# CCM_0024.net
KiCad netlist of a schematic drawn in EAGLE
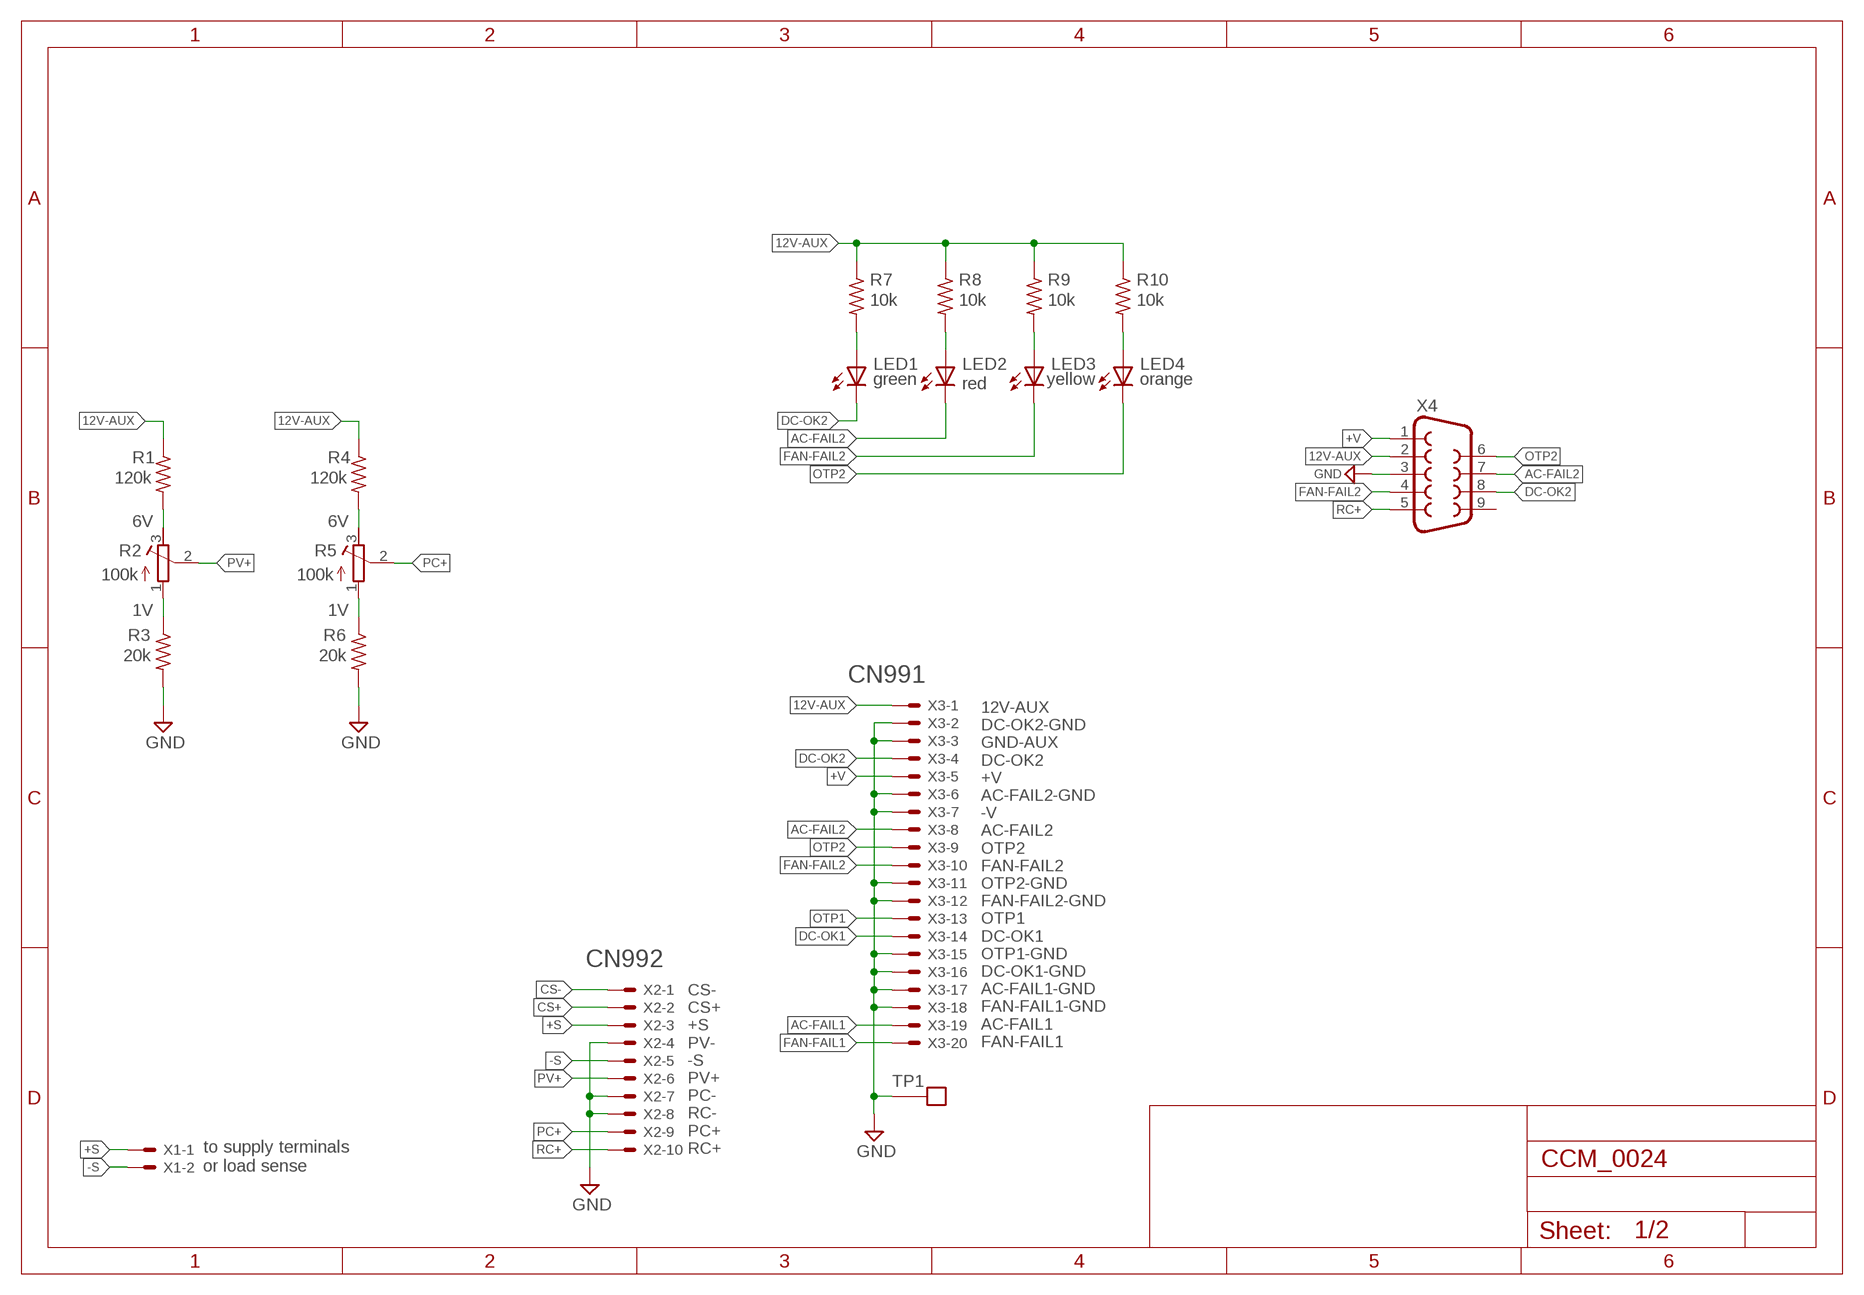
[diagram p0: schematic, sheet 1]
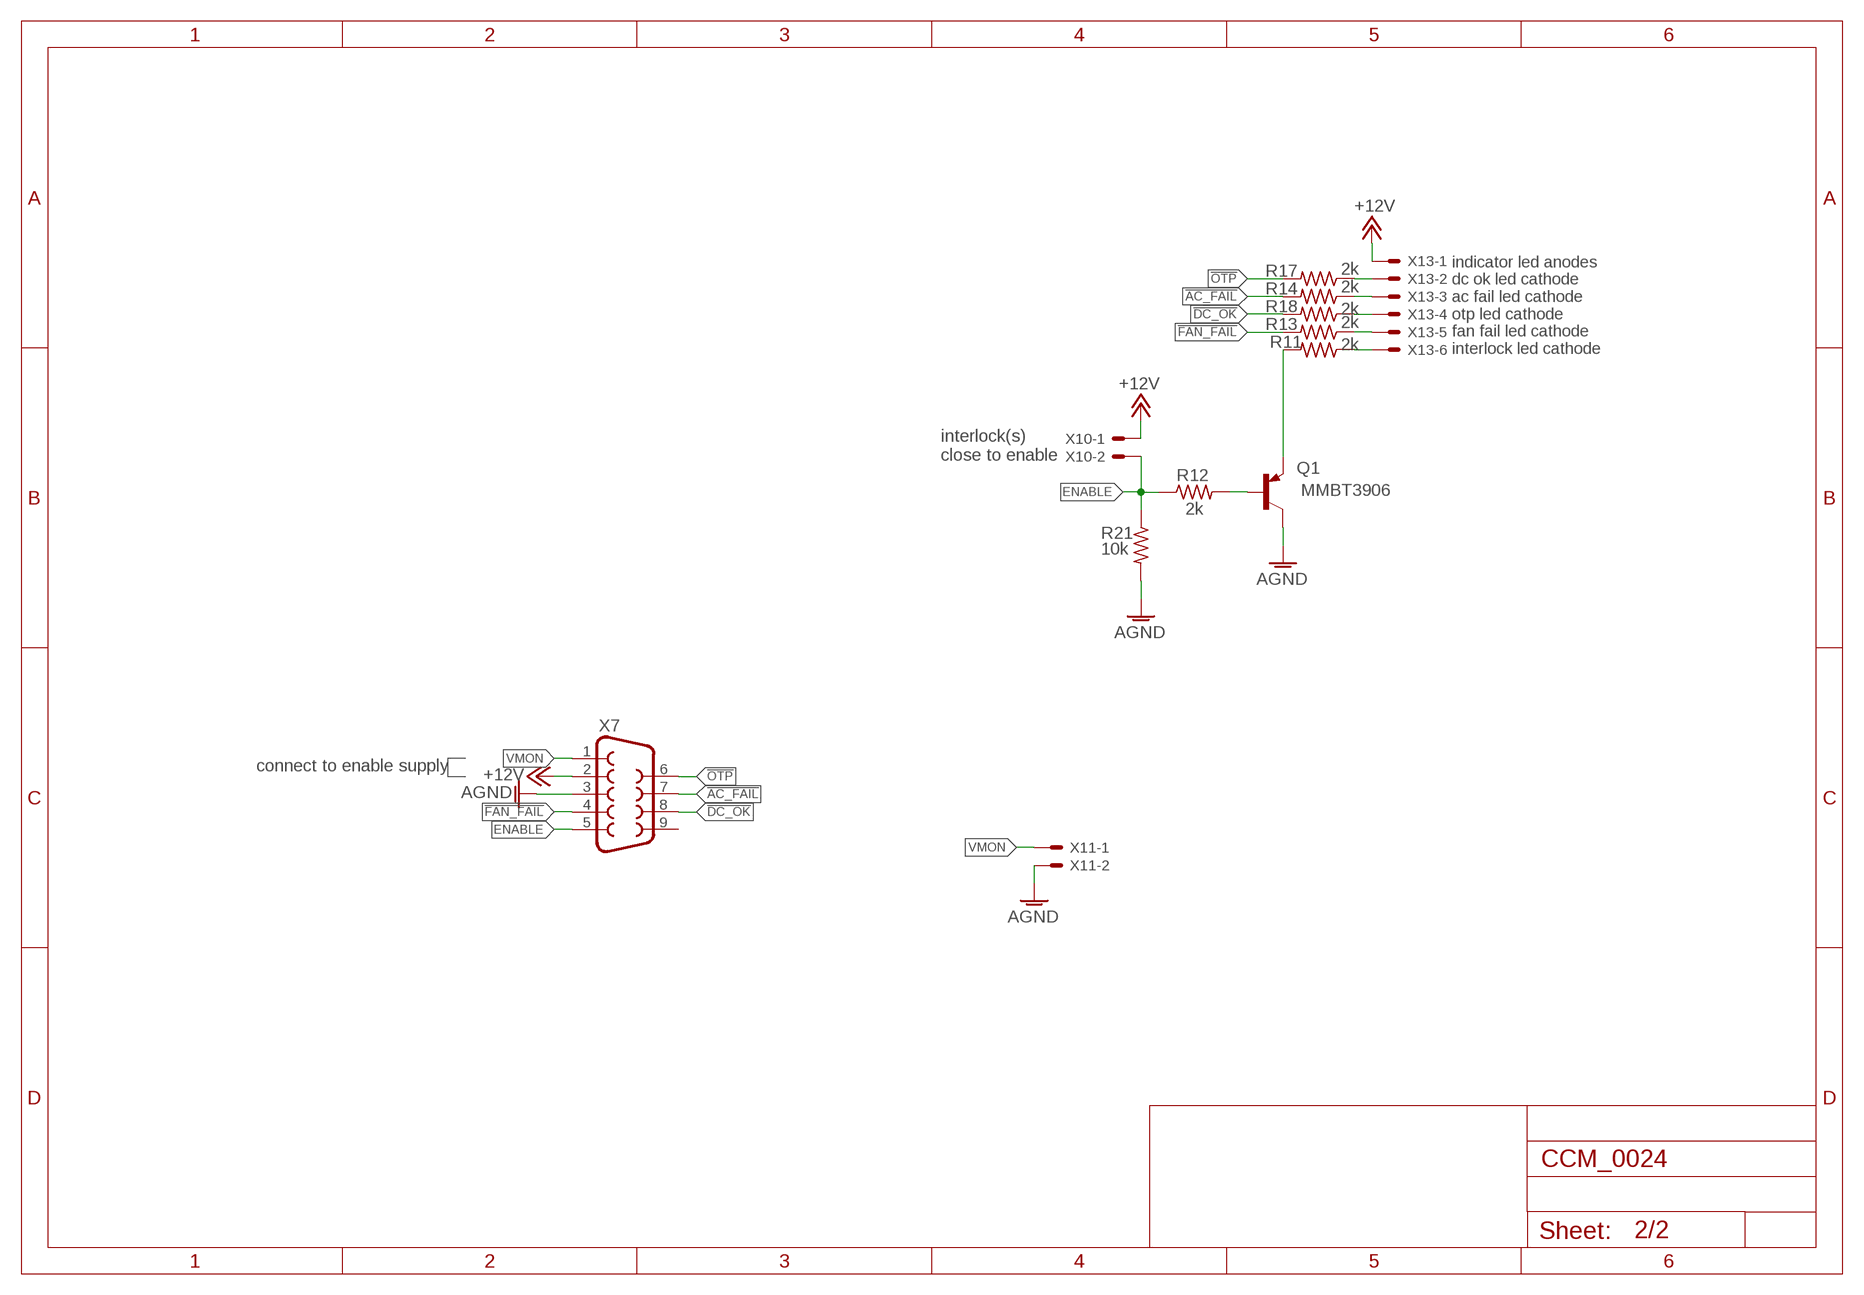
[diagram p1: schematic, sheet 2]

(export (version "E")
  (design (tool "Eeschema 10.0.6"))
  (components
    (comp (ref "Q1")
      (value "MMBT3906")
      (footprint "eagle-import:SOT23-BEC")
      (libsource (lib "eagle-import") (part "MMBT3906SMDLT1"))
    )
    (comp (ref "R11")
      (value "2k")
      (footprint "eagle-import:0603")
      (libsource (lib "eagle-import") (part "R0603"))
    )
    (comp (ref "R12")
      (value "2k")
      (footprint "eagle-import:0603")
      (libsource (lib "eagle-import") (part "R0603"))
    )
    (comp (ref "R13")
      (value "2k")
      (footprint "eagle-import:0603")
      (libsource (lib "eagle-import") (part "R0603"))
    )
    (comp (ref "R14")
      (value "2k")
      (footprint "eagle-import:0603")
      (libsource (lib "eagle-import") (part "R0603"))
    )
    (comp (ref "R17")
      (value "2k")
      (footprint "eagle-import:0603")
      (libsource (lib "eagle-import") (part "R0603"))
    )
    (comp (ref "R18")
      (value "2k")
      (footprint "eagle-import:0603")
      (libsource (lib "eagle-import") (part "R0603"))
    )
    (comp (ref "R21")
      (value "10k")
      (footprint "eagle-import:0603")
      (libsource (lib "eagle-import") (part "R0603"))
    )
    (comp (ref "X7")
      (value "F09H")
      (footprint "eagle-import:F09H")
      (libsource (lib "eagle-import") (part "F09H"))
    )
    (comp (ref "X10")
      (value "22-23-2021")
      (footprint "eagle-import:22-23-2021")
      (fields (field (name "MF") "MOLEX"))
      (libsource (lib "eagle-import") (part "22-23-2021"))
    )
    (comp (ref "X11")
      (value "22-23-2021")
      (footprint "eagle-import:22-23-2021")
      (fields (field (name "MF") "MOLEX"))
      (libsource (lib "eagle-import") (part "22-23-2021"))
    )
    (comp (ref "X13")
      (value "22-23-2061")
      (footprint "eagle-import:22-23-2061")
      (fields (field (name "MF") "MOLEX"))
      (libsource (lib "eagle-import") (part "22-23-2061"))
    )
    (comp (ref "LED1")
      (value "green")
      (footprint "eagle-import:LED_SML0603")
      (libsource (lib "eagle-import") (part "LED_ESML0603"))
    )
    (comp (ref "LED2")
      (value "red")
      (footprint "eagle-import:LED_SML0603")
      (libsource (lib "eagle-import") (part "LED_ESML0603"))
    )
    (comp (ref "LED3")
      (value "yellow")
      (footprint "eagle-import:LED_SML0603")
      (libsource (lib "eagle-import") (part "LED_ESML0603"))
    )
    (comp (ref "LED4")
      (value "orange")
      (footprint "eagle-import:LED_SML0603")
      (libsource (lib "eagle-import") (part "LED_ESML0603"))
    )
    (comp (ref "R1")
      (value "120k")
      (footprint "eagle-import:0603")
      (libsource (lib "eagle-import") (part "R0603"))
    )
    (comp (ref "R2")
      (value "100k")
      (footprint "eagle-import:RTRIM3296Y")
      (libsource (lib "eagle-import") (part "R-TRIMM3296Y"))
    )
    (comp (ref "R3")
      (value "20k")
      (footprint "eagle-import:0603")
      (libsource (lib "eagle-import") (part "R0603"))
    )
    (comp (ref "R4")
      (value "120k")
      (footprint "eagle-import:0603")
      (libsource (lib "eagle-import") (part "R0603"))
    )
    (comp (ref "R5")
      (value "100k")
      (footprint "eagle-import:RTRIM3296Y")
      (libsource (lib "eagle-import") (part "R-TRIMM3296Y"))
    )
    (comp (ref "R6")
      (value "20k")
      (footprint "eagle-import:0603")
      (libsource (lib "eagle-import") (part "R0603"))
    )
    (comp (ref "R7")
      (value "10k")
      (footprint "eagle-import:0603")
      (libsource (lib "eagle-import") (part "R0603"))
    )
    (comp (ref "R8")
      (value "10k")
      (footprint "eagle-import:0603")
      (libsource (lib "eagle-import") (part "R0603"))
    )
    (comp (ref "R9")
      (value "10k")
      (footprint "eagle-import:0603")
      (libsource (lib "eagle-import") (part "R0603"))
    )
    (comp (ref "R10")
      (value "10k")
      (footprint "eagle-import:0603")
      (libsource (lib "eagle-import") (part "R0603"))
    )
    (comp (ref "TP1")
      (value "TESTPOINT")
      (footprint "eagle-import:TESTPOINT")
      (libsource (lib "eagle-import") (part "TESTPOINT"))
    )
    (comp (ref "X1")
      (value "22-23-2021")
      (footprint "eagle-import:22-23-2021")
      (fields (field (name "MF") "MOLEX"))
      (libsource (lib "eagle-import") (part "22-23-2021"))
    )
    (comp (ref "X2")
      (value "87758-1016")
      (footprint "eagle-import:87758-1016")
      (fields (field (name "MF") "MOLEX"))
      (libsource (lib "eagle-import") (part "87758-1016"))
    )
    (comp (ref "X3")
      (value "87758-2016")
      (footprint "eagle-import:87758-2016")
      (fields (field (name "MF") "MOLEX"))
      (libsource (lib "eagle-import") (part "87758-2016"))
    )
    (comp (ref "X4")
      (value "F09V")
      (footprint "eagle-import:F09V")
      (libsource (lib "eagle-import") (part "F09V"))
    )
  )
  (nets
    (net (code "1") (name "+12V") (class "Default")
      (node (ref "X10") (pin "1") (pinfunction "S_1") (pintype "passive"))
      (node (ref "X13") (pin "1") (pinfunction "S_1") (pintype "passive"))
      (node (ref "X7") (pin "2") (pinfunction "2_2") (pintype "passive"))
    )
    (net (code "2") (name "+S") (class "Default")
      (node (ref "X1") (pin "1") (pinfunction "S_1") (pintype "passive"))
      (node (ref "X2") (pin "3") (pinfunction "S_3") (pintype "passive"))
    )
    (net (code "3") (name "+V") (class "Default")
      (node (ref "X3") (pin "5") (pinfunction "S_5") (pintype "passive"))
      (node (ref "X4") (pin "1") (pinfunction "1_1") (pintype "passive"))
    )
    (net (code "4") (name "-S") (class "Default")
      (node (ref "X1") (pin "2") (pinfunction "S_2") (pintype "passive"))
      (node (ref "X2") (pin "5") (pinfunction "S_5") (pintype "passive"))
    )
    (net (code "5") (name "12V-AUX") (class "Default")
      (node (ref "R1") (pin "1") (pinfunction "1_1") (pintype "passive"))
      (node (ref "R10") (pin "1") (pinfunction "1_1") (pintype "passive"))
      (node (ref "R4") (pin "1") (pinfunction "1_1") (pintype "passive"))
      (node (ref "R7") (pin "1") (pinfunction "1_1") (pintype "passive"))
      (node (ref "R8") (pin "1") (pinfunction "1_1") (pintype "passive"))
      (node (ref "R9") (pin "1") (pinfunction "1_1") (pintype "passive"))
      (node (ref "X3") (pin "1") (pinfunction "S_1") (pintype "passive"))
      (node (ref "X4") (pin "2") (pinfunction "2_2") (pintype "passive"))
    )
    (net (code "6") (name "AC-FAIL1") (class "Default")
      (node (ref "X3") (pin "19") (pinfunction "S_19") (pintype "passive"))
    )
    (net (code "7") (name "AC-FAIL2") (class "Default")
      (node (ref "LED2") (pin "C") (pinfunction "C_C") (pintype "passive"))
      (node (ref "X3") (pin "8") (pinfunction "S_8") (pintype "passive"))
      (node (ref "X4") (pin "7") (pinfunction "7_7") (pintype "passive"))
    )
    (net (code "8") (name "AGND") (class "Default")
      (node (ref "Q1") (pin "C") (pinfunction "C_C") (pintype "passive"))
      (node (ref "R21") (pin "2") (pinfunction "2_2") (pintype "passive"))
      (node (ref "X11") (pin "2") (pinfunction "S_2") (pintype "passive"))
      (node (ref "X7") (pin "3") (pinfunction "3_3") (pintype "passive"))
    )
    (net (code "9") (name "CS+") (class "Default")
      (node (ref "X2") (pin "2") (pinfunction "S_2") (pintype "passive"))
    )
    (net (code "10") (name "CS-") (class "Default")
      (node (ref "X2") (pin "1") (pinfunction "S_1") (pintype "passive"))
    )
    (net (code "11") (name "DC-OK1") (class "Default")
      (node (ref "X3") (pin "14") (pinfunction "S_14") (pintype "passive"))
    )
    (net (code "12") (name "DC-OK2") (class "Default")
      (node (ref "LED1") (pin "C") (pinfunction "C_C") (pintype "passive"))
      (node (ref "X3") (pin "4") (pinfunction "S_4") (pintype "passive"))
      (node (ref "X4") (pin "8") (pinfunction "8_8") (pintype "passive"))
    )
    (net (code "13") (name "ENABLE") (class "Default")
      (node (ref "R12") (pin "1") (pinfunction "1_1") (pintype "passive"))
      (node (ref "R21") (pin "1") (pinfunction "1_1") (pintype "passive"))
      (node (ref "X10") (pin "2") (pinfunction "S_2") (pintype "passive"))
      (node (ref "X7") (pin "5") (pinfunction "5_5") (pintype "passive"))
    )
    (net (code "14") (name "FAN-FAIL1") (class "Default")
      (node (ref "X3") (pin "20") (pinfunction "S_20") (pintype "passive"))
    )
    (net (code "15") (name "FAN-FAIL2") (class "Default")
      (node (ref "LED3") (pin "C") (pinfunction "C_C") (pintype "passive"))
      (node (ref "X3") (pin "10") (pinfunction "S_10") (pintype "passive"))
      (node (ref "X4") (pin "4") (pinfunction "4_4") (pintype "passive"))
    )
    (net (code "16") (name "GND") (class "Default")
      (node (ref "R3") (pin "2") (pinfunction "2_2") (pintype "passive"))
      (node (ref "R6") (pin "2") (pinfunction "2_2") (pintype "passive"))
      (node (ref "TP1") (pin "P$1") (pinfunction "P$1_P$1") (pintype "bidirectional"))
      (node (ref "X2") (pin "4") (pinfunction "S_4") (pintype "passive"))
      (node (ref "X2") (pin "7") (pinfunction "S_7") (pintype "passive"))
      (node (ref "X2") (pin "8") (pinfunction "S_8") (pintype "passive"))
      (node (ref "X3") (pin "11") (pinfunction "S_11") (pintype "passive"))
      (node (ref "X3") (pin "12") (pinfunction "S_12") (pintype "passive"))
      (node (ref "X3") (pin "15") (pinfunction "S_15") (pintype "passive"))
      (node (ref "X3") (pin "16") (pinfunction "S_16") (pintype "passive"))
      (node (ref "X3") (pin "17") (pinfunction "S_17") (pintype "passive"))
      (node (ref "X3") (pin "18") (pinfunction "S_18") (pintype "passive"))
      (node (ref "X3") (pin "2") (pinfunction "S_2") (pintype "passive"))
      (node (ref "X3") (pin "3") (pinfunction "S_3") (pintype "passive"))
      (node (ref "X3") (pin "6") (pinfunction "S_6") (pintype "passive"))
      (node (ref "X3") (pin "7") (pinfunction "S_7") (pintype "passive"))
      (node (ref "X4") (pin "3") (pinfunction "3_3") (pintype "passive"))
    )
    (net (code "17") (name "Net-(LED1-PadA)") (class "Default")
      (node (ref "LED1") (pin "A") (pinfunction "A_A") (pintype "passive"))
      (node (ref "R7") (pin "2") (pinfunction "2_2") (pintype "passive"))
    )
    (net (code "18") (name "Net-(LED2-PadA)") (class "Default")
      (node (ref "LED2") (pin "A") (pinfunction "A_A") (pintype "passive"))
      (node (ref "R8") (pin "2") (pinfunction "2_2") (pintype "passive"))
    )
    (net (code "19") (name "Net-(LED3-PadA)") (class "Default")
      (node (ref "LED3") (pin "A") (pinfunction "A_A") (pintype "passive"))
      (node (ref "R9") (pin "2") (pinfunction "2_2") (pintype "passive"))
    )
    (net (code "20") (name "Net-(LED4-PadA)") (class "Default")
      (node (ref "LED4") (pin "A") (pinfunction "A_A") (pintype "passive"))
      (node (ref "R10") (pin "2") (pinfunction "2_2") (pintype "passive"))
    )
    (net (code "21") (name "Net-(Q1-PadB)") (class "Default")
      (node (ref "Q1") (pin "B") (pinfunction "B_B") (pintype "passive"))
      (node (ref "R12") (pin "2") (pinfunction "2_2") (pintype "passive"))
    )
    (net (code "22") (name "Net-(Q1-PadE)") (class "Default")
      (node (ref "Q1") (pin "E") (pinfunction "E_E") (pintype "passive"))
      (node (ref "R11") (pin "2") (pinfunction "2_2") (pintype "passive"))
    )
    (net (code "23") (name "Net-(R2-A)") (class "Default")
      (node (ref "R2") (pin "1") (pinfunction "A_1") (pintype "passive"))
      (node (ref "R3") (pin "1") (pinfunction "1_1") (pintype "passive"))
    )
    (net (code "24") (name "Net-(R2-E)") (class "Default")
      (node (ref "R1") (pin "2") (pinfunction "2_2") (pintype "passive"))
      (node (ref "R2") (pin "3") (pinfunction "E_3") (pintype "passive"))
    )
    (net (code "25") (name "Net-(R5-A)") (class "Default")
      (node (ref "R5") (pin "1") (pinfunction "A_1") (pintype "passive"))
      (node (ref "R6") (pin "1") (pinfunction "1_1") (pintype "passive"))
    )
    (net (code "26") (name "Net-(R5-E)") (class "Default")
      (node (ref "R4") (pin "2") (pinfunction "2_2") (pintype "passive"))
      (node (ref "R5") (pin "3") (pinfunction "E_3") (pintype "passive"))
    )
    (net (code "27") (name "Net-(X13B-S)") (class "Default")
      (node (ref "R17") (pin "1") (pinfunction "1_1") (pintype "passive"))
      (node (ref "X13") (pin "2") (pinfunction "S_2") (pintype "passive"))
    )
    (net (code "28") (name "Net-(X13C-S)") (class "Default")
      (node (ref "R14") (pin "1") (pinfunction "1_1") (pintype "passive"))
      (node (ref "X13") (pin "3") (pinfunction "S_3") (pintype "passive"))
    )
    (net (code "29") (name "Net-(X13D-S)") (class "Default")
      (node (ref "R18") (pin "1") (pinfunction "1_1") (pintype "passive"))
      (node (ref "X13") (pin "4") (pinfunction "S_4") (pintype "passive"))
    )
    (net (code "30") (name "Net-(X13E-S)") (class "Default")
      (node (ref "R13") (pin "1") (pinfunction "1_1") (pintype "passive"))
      (node (ref "X13") (pin "5") (pinfunction "S_5") (pintype "passive"))
    )
    (net (code "31") (name "Net-(X13F-S)") (class "Default")
      (node (ref "R11") (pin "1") (pinfunction "1_1") (pintype "passive"))
      (node (ref "X13") (pin "6") (pinfunction "S_6") (pintype "passive"))
    )
    (net (code "32") (name "OTP1") (class "Default")
      (node (ref "X3") (pin "13") (pinfunction "S_13") (pintype "passive"))
    )
    (net (code "33") (name "OTP2") (class "Default")
      (node (ref "LED4") (pin "C") (pinfunction "C_C") (pintype "passive"))
      (node (ref "X3") (pin "9") (pinfunction "S_9") (pintype "passive"))
      (node (ref "X4") (pin "6") (pinfunction "6_6") (pintype "passive"))
    )
    (net (code "34") (name "PC+") (class "Default")
      (node (ref "R5") (pin "2") (pinfunction "S_2") (pintype "passive"))
      (node (ref "X2") (pin "9") (pinfunction "S_9") (pintype "passive"))
    )
    (net (code "35") (name "PV+") (class "Default")
      (node (ref "R2") (pin "2") (pinfunction "S_2") (pintype "passive"))
      (node (ref "X2") (pin "6") (pinfunction "S_6") (pintype "passive"))
    )
    (net (code "36") (name "RC+") (class "Default")
      (node (ref "X2") (pin "10") (pinfunction "S_10") (pintype "passive"))
      (node (ref "X4") (pin "5") (pinfunction "5_5") (pintype "passive"))
    )
    (net (code "37") (name "VMON") (class "Default")
      (node (ref "X11") (pin "1") (pinfunction "S_1") (pintype "passive"))
      (node (ref "X7") (pin "1") (pinfunction "1_1") (pintype "passive"))
    )
    (net (code "38") (name "unconnected-(X4-Pad9)") (class "Default")
      (node (ref "X4") (pin "9") (pinfunction "9_9") (pintype "passive"))
    )
    (net (code "39") (name "unconnected-(X7-Pad9)") (class "Default")
      (node (ref "X7") (pin "9") (pinfunction "9_9") (pintype "passive"))
    )
    (net (code "40") (name "~{AC_FAIL}") (class "Default")
      (node (ref "R14") (pin "2") (pinfunction "2_2") (pintype "passive"))
      (node (ref "X7") (pin "7") (pinfunction "7_7") (pintype "passive"))
    )
    (net (code "41") (name "~{DC_OK}") (class "Default")
      (node (ref "R18") (pin "2") (pinfunction "2_2") (pintype "passive"))
      (node (ref "X7") (pin "8") (pinfunction "8_8") (pintype "passive"))
    )
    (net (code "42") (name "~{FAN_FAIL}") (class "Default")
      (node (ref "R13") (pin "2") (pinfunction "2_2") (pintype "passive"))
      (node (ref "X7") (pin "4") (pinfunction "4_4") (pintype "passive"))
    )
    (net (code "43") (name "~{OTP}") (class "Default")
      (node (ref "R17") (pin "2") (pinfunction "2_2") (pintype "passive"))
      (node (ref "X7") (pin "6") (pinfunction "6_6") (pintype "passive"))
    )
  )
)
